# 1x9x1.net
KiCad netlist of a schematic drawn in Altium Designer
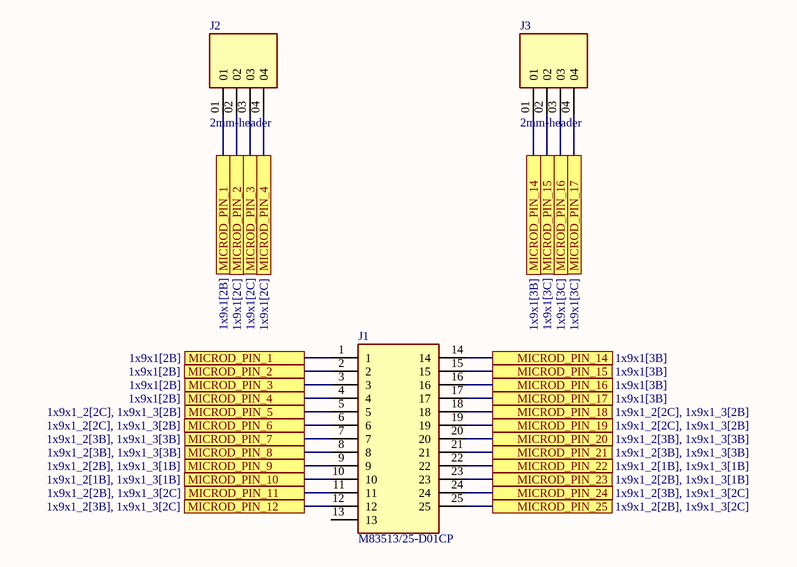
[diagram p0: 1x9x1.SchDoc]

(export (version "E")
  (design (tool "Eeschema 10.0.6"))
  (components
    (comp (ref "J1")
      (value "M83513/25-D01CP")
      (footprint "BEL_M83513/25-D01CP")
      (libsource (lib "SchlibLafe") (part "M83513/25-D01CP"))
    )
    (comp (ref "J2")
      (value "2mm-header")
      (footprint "2mm-header")
      (fields (field (name "MP") "altium_native_batch"))
      (libsource (lib "SchlibLafe") (part "2mm-header"))
    )
    (comp (ref "J3")
      (value "2mm-header")
      (footprint "2mm-header")
      (fields (field (name "MP") "altium_native_batch"))
      (libsource (lib "SchlibLafe") (part "2mm-header"))
    )
  )
  (nets
    (net (code "1") (name "/MICROD_PIN_1") (class "Default")
      (node (ref "J1") (pin "1") (pinfunction "1_1") (pintype "passive"))
      (node (ref "J2") (pin "01") (pinfunction "01_01") (pintype "passive"))
    )
    (net (code "2") (name "/MICROD_PIN_2") (class "Default")
      (node (ref "J1") (pin "2") (pinfunction "2_2") (pintype "passive"))
      (node (ref "J2") (pin "02") (pinfunction "02_02") (pintype "passive"))
    )
    (net (code "3") (name "/MICROD_PIN_3") (class "Default")
      (node (ref "J1") (pin "3") (pinfunction "3_3") (pintype "passive"))
      (node (ref "J2") (pin "03") (pinfunction "03_03") (pintype "passive"))
    )
    (net (code "4") (name "/MICROD_PIN_4") (class "Default")
      (node (ref "J1") (pin "4") (pinfunction "4_4") (pintype "passive"))
      (node (ref "J2") (pin "04") (pinfunction "04_04") (pintype "passive"))
    )
    (net (code "5") (name "/MICROD_PIN_5") (class "Default")
      (node (ref "J1") (pin "5") (pinfunction "5_5") (pintype "passive"))
    )
    (net (code "6") (name "/MICROD_PIN_6") (class "Default")
      (node (ref "J1") (pin "6") (pinfunction "6_6") (pintype "passive"))
    )
    (net (code "7") (name "/MICROD_PIN_7") (class "Default")
      (node (ref "J1") (pin "7") (pinfunction "7_7") (pintype "passive"))
    )
    (net (code "8") (name "/MICROD_PIN_8") (class "Default")
      (node (ref "J1") (pin "8") (pinfunction "8_8") (pintype "passive"))
    )
    (net (code "9") (name "/MICROD_PIN_9") (class "Default")
      (node (ref "J1") (pin "9") (pinfunction "9_9") (pintype "passive"))
    )
    (net (code "10") (name "/MICROD_PIN_10") (class "Default")
      (node (ref "J1") (pin "10") (pinfunction "10_10") (pintype "passive"))
    )
    (net (code "11") (name "/MICROD_PIN_11") (class "Default")
      (node (ref "J1") (pin "11") (pinfunction "11_11") (pintype "passive"))
    )
    (net (code "12") (name "/MICROD_PIN_12") (class "Default")
      (node (ref "J1") (pin "12") (pinfunction "12_12") (pintype "passive"))
    )
    (net (code "13") (name "/MICROD_PIN_14") (class "Default")
      (node (ref "J1") (pin "14") (pinfunction "14_14") (pintype "passive"))
      (node (ref "J3") (pin "01") (pinfunction "01_01") (pintype "passive"))
    )
    (net (code "14") (name "/MICROD_PIN_15") (class "Default")
      (node (ref "J1") (pin "15") (pinfunction "15_15") (pintype "passive"))
      (node (ref "J3") (pin "02") (pinfunction "02_02") (pintype "passive"))
    )
    (net (code "15") (name "/MICROD_PIN_16") (class "Default")
      (node (ref "J1") (pin "16") (pinfunction "16_16") (pintype "passive"))
      (node (ref "J3") (pin "03") (pinfunction "03_03") (pintype "passive"))
    )
    (net (code "16") (name "/MICROD_PIN_17") (class "Default")
      (node (ref "J1") (pin "17") (pinfunction "17_17") (pintype "passive"))
      (node (ref "J3") (pin "04") (pinfunction "04_04") (pintype "passive"))
    )
    (net (code "17") (name "/MICROD_PIN_18") (class "Default")
      (node (ref "J1") (pin "18") (pinfunction "18_18") (pintype "passive"))
    )
    (net (code "18") (name "/MICROD_PIN_19") (class "Default")
      (node (ref "J1") (pin "19") (pinfunction "19_19") (pintype "passive"))
    )
    (net (code "19") (name "/MICROD_PIN_20") (class "Default")
      (node (ref "J1") (pin "20") (pinfunction "20_20") (pintype "passive"))
    )
    (net (code "20") (name "/MICROD_PIN_21") (class "Default")
      (node (ref "J1") (pin "21") (pinfunction "21_21") (pintype "passive"))
    )
    (net (code "21") (name "/MICROD_PIN_22") (class "Default")
      (node (ref "J1") (pin "22") (pinfunction "22_22") (pintype "passive"))
    )
    (net (code "22") (name "/MICROD_PIN_23") (class "Default")
      (node (ref "J1") (pin "23") (pinfunction "23_23") (pintype "passive"))
    )
    (net (code "23") (name "/MICROD_PIN_24") (class "Default")
      (node (ref "J1") (pin "24") (pinfunction "24_24") (pintype "passive"))
    )
    (net (code "24") (name "/MICROD_PIN_25") (class "Default")
      (node (ref "J1") (pin "25") (pinfunction "25_25") (pintype "passive"))
    )
    (net (code "25") (name "unconnected-(J1-Pad13)") (class "Default")
      (node (ref "J1") (pin "13") (pinfunction "13_13") (pintype "passive"))
    )
  )
)
